# VibrationDrive1.net
KiCad netlist of a schematic drawn in EAGLE
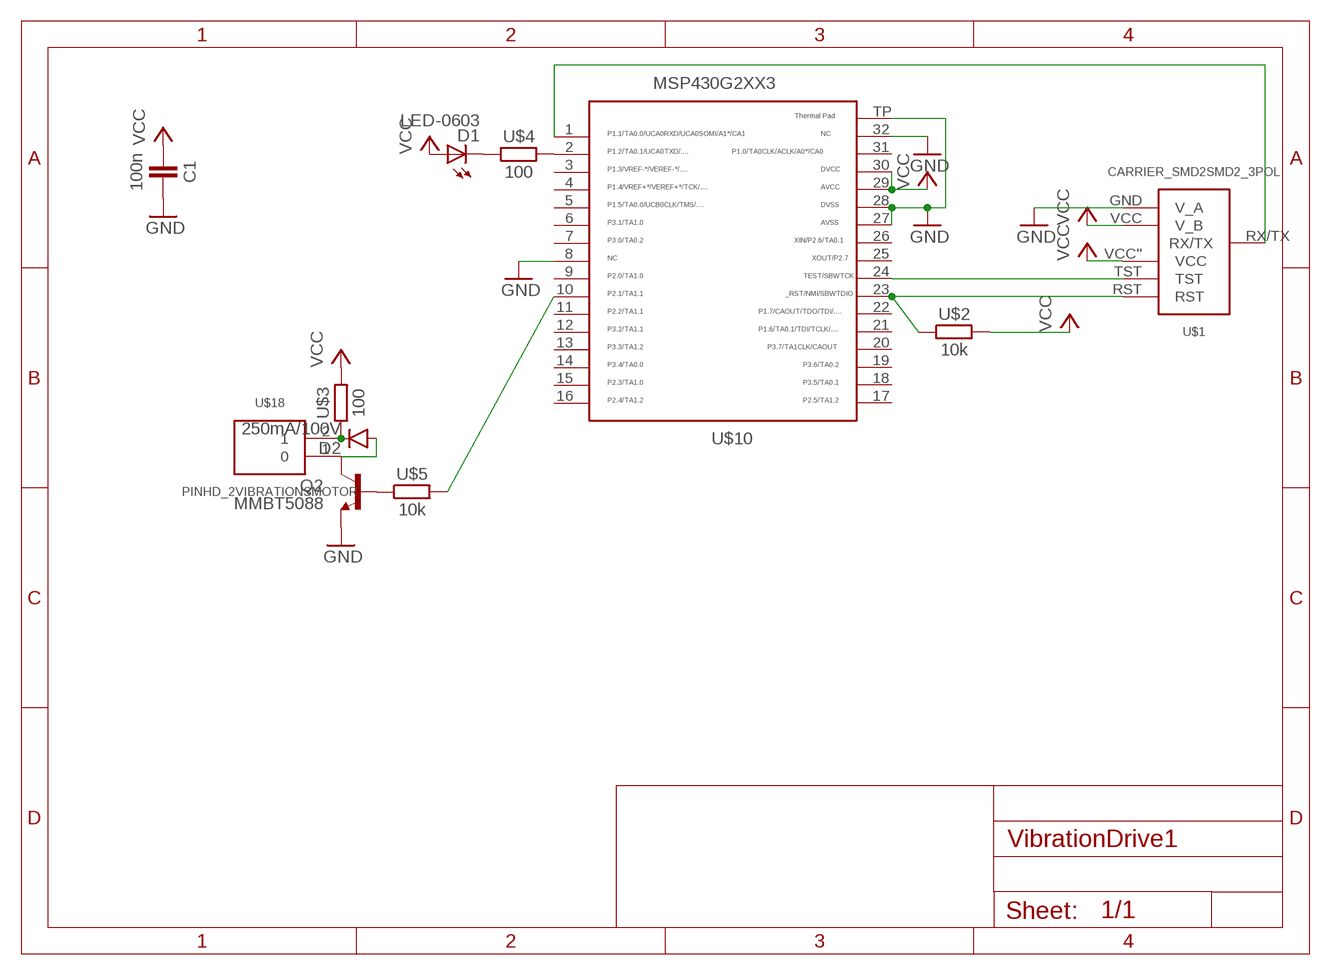
[diagram p0: schematic, sheet 1]

(export (version "E")
  (design (tool "Eeschema 10.0.6"))
  (components
    (comp (ref "C1")
      (value "100n")
      (footprint "eagle-import:603")
      (libsource (lib "eagle-import") (part "CAPACITOR"))
    )
    (comp (ref "D1")
      (value "LED-0603")
      (footprint "eagle-import:LED_0603")
      (libsource (lib "eagle-import") (part "LED-0603"))
    )
    (comp (ref "D2")
      (value "250mA/100V")
      (footprint "eagle-import:SOD-323")
      (libsource (lib "eagle-import") (part "DIODEBAS16"))
    )
    (comp (ref "Q2")
      (value "MMBT5088")
      (footprint "eagle-import:SOT23-3")
      (libsource (lib "eagle-import") (part "TRANSISTOR_NPNMMBT5088"))
    )
    (comp (ref "U$1")
      (value "CARRIER_SMD2SMD2_3POL")
      (footprint "eagle-import:CARRIER_SMD2_3POL")
      (libsource (lib "eagle-import") (part "CARRIER_SMD2SMD2_3POL"))
    )
    (comp (ref "U$2")
      (value "10k")
      (footprint "eagle-import:603")
      (libsource (lib "eagle-import") (part "RESISTOR0603"))
    )
    (comp (ref "U$3")
      (value "100")
      (footprint "eagle-import:603")
      (libsource (lib "eagle-import") (part "RESISTOR0603"))
    )
    (comp (ref "U$4")
      (value "100")
      (footprint "eagle-import:603")
      (libsource (lib "eagle-import") (part "RESISTOR0603"))
    )
    (comp (ref "U$5")
      (value "10k")
      (footprint "eagle-import:603")
      (libsource (lib "eagle-import") (part "RESISTOR0603"))
    )
    (comp (ref "U$10")
      (value "MSP430G2553")
      (footprint "eagle-import:QFN32")
      (libsource (lib "eagle-import") (part "MSP430G2553"))
    )
    (comp (ref "U$18")
      (value "PINHD_2VIBRATIONSMOTOR")
      (footprint "eagle-import:VIBRATIONSMOTOR")
      (libsource (lib "eagle-import") (part "PINHD_2VIBRATIONSMOTOR"))
    )
  )
  (nets
    (net (code "1") (name "GND") (class "Default")
      (node (ref "C1") (pin "2") (pinfunction "2_2") (pintype "passive"))
      (node (ref "Q2") (pin "2") (pinfunction "E_2") (pintype "passive"))
      (node (ref "U$1") (pin "GND") (pinfunction "V_A_GND") (pintype "bidirectional"))
      (node (ref "U$10") (pin "27") (pinfunction "27_27") (pintype "bidirectional"))
      (node (ref "U$10") (pin "28") (pinfunction "28_28") (pintype "bidirectional"))
      (node (ref "U$10") (pin "32") (pinfunction "32_32") (pintype "bidirectional"))
      (node (ref "U$10") (pin "8") (pinfunction "8_8") (pintype "bidirectional"))
      (node (ref "U$10") (pin "TP") (pinfunction "TP_TP") (pintype "bidirectional"))
    )
    (net (code "2") (name "Net-(D1-PadC)") (class "Default")
      (node (ref "D1") (pin "C") (pinfunction "C_C") (pintype "passive"))
      (node (ref "U$4") (pin "1") (pinfunction "1_1") (pintype "passive"))
    )
    (net (code "3") (name "Net-(Q2-B)") (class "Default")
      (node (ref "Q2") (pin "1") (pinfunction "B_1") (pintype "passive"))
      (node (ref "U$5") (pin "1") (pinfunction "1_1") (pintype "passive"))
    )
    (net (code "4") (name "Net-(Q2-C)") (class "Default")
      (node (ref "D2") (pin "A") (pinfunction "A_A") (pintype "passive"))
      (node (ref "Q2") (pin "3") (pinfunction "C_3") (pintype "passive"))
      (node (ref "U$18") (pin "1") (pinfunction "0_1") (pintype "bidirectional"))
    )
    (net (code "5") (name "Net-(U$1-PadRST)") (class "Default")
      (node (ref "U$1") (pin "RST") (pinfunction "RST_RST") (pintype "bidirectional"))
      (node (ref "U$10") (pin "23") (pinfunction "23_23") (pintype "bidirectional"))
      (node (ref "U$2") (pin "1") (pinfunction "1_1") (pintype "passive"))
    )
    (net (code "6") (name "Net-(U$1-PadRX{slash}TX)") (class "Default")
      (node (ref "U$1") (pin "RX/TX") (pinfunction "RX/TX_RX/TX") (pintype "bidirectional"))
      (node (ref "U$10") (pin "1") (pinfunction "1_1") (pintype "bidirectional"))
    )
    (net (code "7") (name "Net-(U$1-PadTST)") (class "Default")
      (node (ref "U$1") (pin "TST") (pinfunction "TST_TST") (pintype "bidirectional"))
      (node (ref "U$10") (pin "24") (pinfunction "24_24") (pintype "bidirectional"))
    )
    (net (code "8") (name "Net-(U$10-Pad2)") (class "Default")
      (node (ref "U$10") (pin "2") (pinfunction "2_2") (pintype "bidirectional"))
      (node (ref "U$4") (pin "2") (pinfunction "2_2") (pintype "passive"))
    )
    (net (code "9") (name "Net-(U$10-Pad10)") (class "Default")
      (node (ref "U$10") (pin "10") (pinfunction "10_10") (pintype "bidirectional"))
      (node (ref "U$5") (pin "2") (pinfunction "2_2") (pintype "passive"))
    )
    (net (code "10") (name "Net-(U$18-1)") (class "Default")
      (node (ref "D2") (pin "C") (pinfunction "C_C") (pintype "passive"))
      (node (ref "U$18") (pin "2") (pinfunction "1_2") (pintype "bidirectional"))
      (node (ref "U$3") (pin "1") (pinfunction "1_1") (pintype "passive"))
    )
    (net (code "11") (name "VCC") (class "Default")
      (node (ref "C1") (pin "1") (pinfunction "1_1") (pintype "passive"))
      (node (ref "D1") (pin "A") (pinfunction "A_A") (pintype "passive"))
      (node (ref "U$1") (pin "VCC") (pinfunction "V_B_VCC") (pintype "bidirectional"))
      (node (ref "U$1") (pin "VCC''") (pinfunction "VCC_VCC''") (pintype "bidirectional"))
      (node (ref "U$10") (pin "29") (pinfunction "29_29") (pintype "bidirectional"))
      (node (ref "U$10") (pin "30") (pinfunction "30_30") (pintype "bidirectional"))
      (node (ref "U$2") (pin "2") (pinfunction "2_2") (pintype "passive"))
      (node (ref "U$3") (pin "2") (pinfunction "2_2") (pintype "passive"))
    )
    (net (code "12") (name "unconnected-(U$10-Pad3)") (class "Default")
      (node (ref "U$10") (pin "3") (pinfunction "3_3") (pintype "bidirectional"))
    )
    (net (code "13") (name "unconnected-(U$10-Pad4)") (class "Default")
      (node (ref "U$10") (pin "4") (pinfunction "4_4") (pintype "bidirectional"))
    )
    (net (code "14") (name "unconnected-(U$10-Pad5)") (class "Default")
      (node (ref "U$10") (pin "5") (pinfunction "5_5") (pintype "bidirectional"))
    )
    (net (code "15") (name "unconnected-(U$10-Pad6)") (class "Default")
      (node (ref "U$10") (pin "6") (pinfunction "6_6") (pintype "bidirectional"))
    )
    (net (code "16") (name "unconnected-(U$10-Pad7)") (class "Default")
      (node (ref "U$10") (pin "7") (pinfunction "7_7") (pintype "bidirectional"))
    )
    (net (code "17") (name "unconnected-(U$10-Pad9)") (class "Default")
      (node (ref "U$10") (pin "9") (pinfunction "9_9") (pintype "bidirectional"))
    )
    (net (code "18") (name "unconnected-(U$10-Pad11)") (class "Default")
      (node (ref "U$10") (pin "11") (pinfunction "11_11") (pintype "bidirectional"))
    )
    (net (code "19") (name "unconnected-(U$10-Pad12)") (class "Default")
      (node (ref "U$10") (pin "12") (pinfunction "12_12") (pintype "bidirectional"))
    )
    (net (code "20") (name "unconnected-(U$10-Pad13)") (class "Default")
      (node (ref "U$10") (pin "13") (pinfunction "13_13") (pintype "bidirectional"))
    )
    (net (code "21") (name "unconnected-(U$10-Pad14)") (class "Default")
      (node (ref "U$10") (pin "14") (pinfunction "14_14") (pintype "bidirectional"))
    )
    (net (code "22") (name "unconnected-(U$10-Pad15)") (class "Default")
      (node (ref "U$10") (pin "15") (pinfunction "15_15") (pintype "bidirectional"))
    )
    (net (code "23") (name "unconnected-(U$10-Pad16)") (class "Default")
      (node (ref "U$10") (pin "16") (pinfunction "16_16") (pintype "bidirectional"))
    )
    (net (code "24") (name "unconnected-(U$10-Pad17)") (class "Default")
      (node (ref "U$10") (pin "17") (pinfunction "17_17") (pintype "bidirectional"))
    )
    (net (code "25") (name "unconnected-(U$10-Pad18)") (class "Default")
      (node (ref "U$10") (pin "18") (pinfunction "18_18") (pintype "bidirectional"))
    )
    (net (code "26") (name "unconnected-(U$10-Pad19)") (class "Default")
      (node (ref "U$10") (pin "19") (pinfunction "19_19") (pintype "bidirectional"))
    )
    (net (code "27") (name "unconnected-(U$10-Pad20)") (class "Default")
      (node (ref "U$10") (pin "20") (pinfunction "20_20") (pintype "bidirectional"))
    )
    (net (code "28") (name "unconnected-(U$10-Pad21)") (class "Default")
      (node (ref "U$10") (pin "21") (pinfunction "21_21") (pintype "bidirectional"))
    )
    (net (code "29") (name "unconnected-(U$10-Pad22)") (class "Default")
      (node (ref "U$10") (pin "22") (pinfunction "22_22") (pintype "bidirectional"))
    )
    (net (code "30") (name "unconnected-(U$10-Pad25)") (class "Default")
      (node (ref "U$10") (pin "25") (pinfunction "25_25") (pintype "bidirectional"))
    )
    (net (code "31") (name "unconnected-(U$10-Pad26)") (class "Default")
      (node (ref "U$10") (pin "26") (pinfunction "26_26") (pintype "bidirectional"))
    )
    (net (code "32") (name "unconnected-(U$10-Pad31)") (class "Default")
      (node (ref "U$10") (pin "31") (pinfunction "31_31") (pintype "bidirectional"))
    )
  )
)
